# TiltyDuo.net
KiCad netlist of a schematic drawn in EAGLE
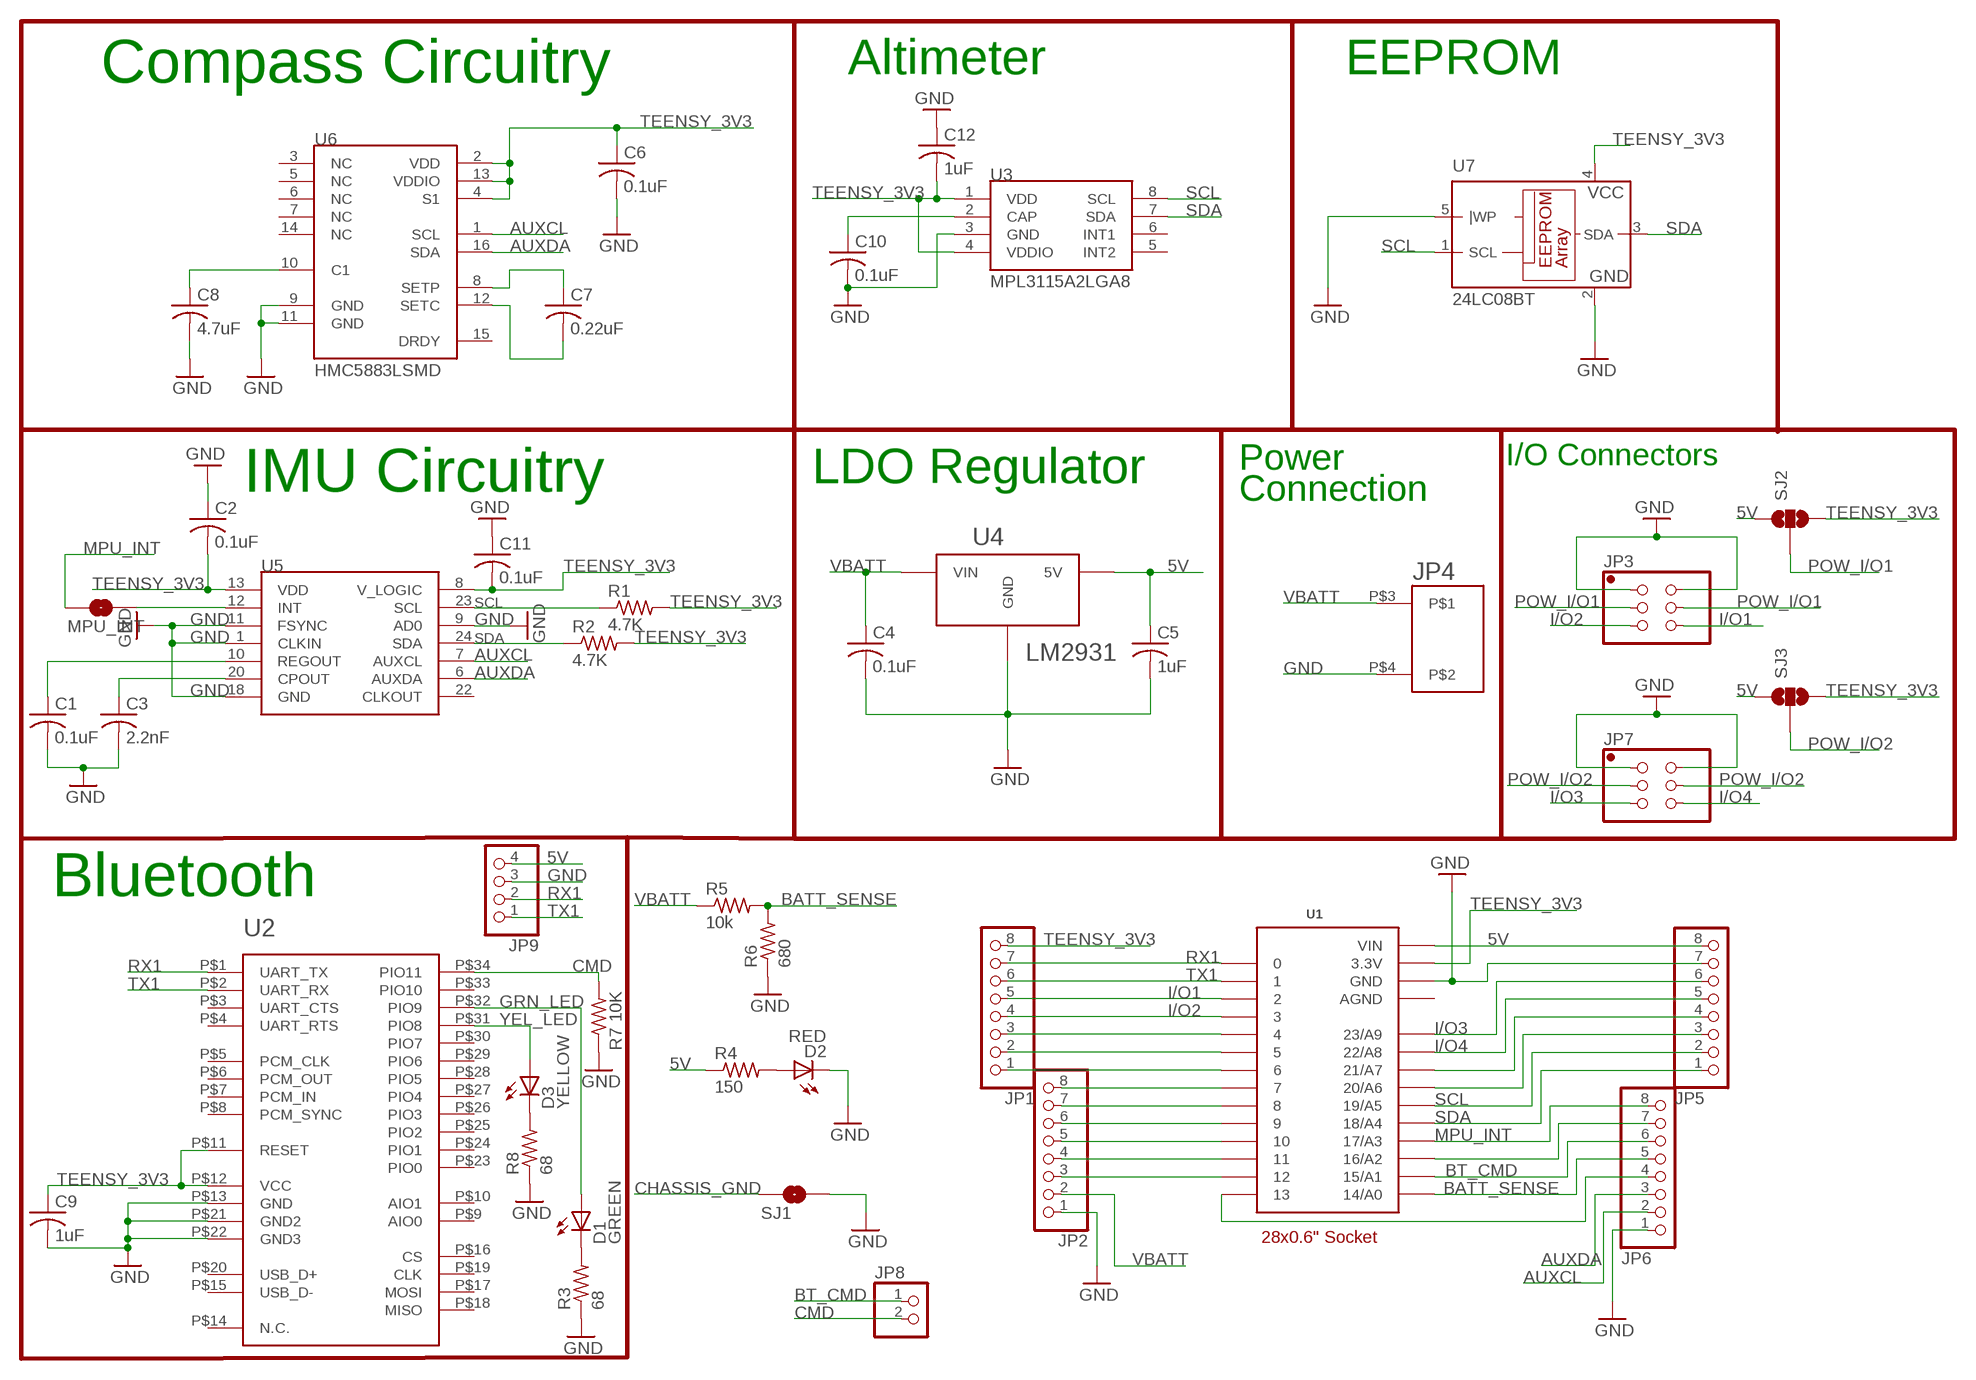
[diagram p0: schematic, sheet 1]

(export (version "E")
  (design (tool "Eeschema 10.0.6"))
  (components
    (comp (ref "C1")
      (value "0.1uF")
      (footprint "eagle-import:C0603")
      (libsource (lib "eagle-import") (part "C-USC0603"))
    )
    (comp (ref "C2")
      (value "0.1uF")
      (footprint "eagle-import:C0603")
      (libsource (lib "eagle-import") (part "C-USC0603"))
    )
    (comp (ref "C3")
      (value "2.2nF")
      (footprint "eagle-import:C0603")
      (libsource (lib "eagle-import") (part "C-USC0603"))
    )
    (comp (ref "C4")
      (value "0.1uF")
      (footprint "eagle-import:C0603")
      (libsource (lib "eagle-import") (part "C-USC0603"))
    )
    (comp (ref "C5")
      (value "1uF")
      (footprint "eagle-import:C0603")
      (libsource (lib "eagle-import") (part "C-USC0603"))
    )
    (comp (ref "C6")
      (value "0.1uF")
      (footprint "eagle-import:C0603")
      (libsource (lib "eagle-import") (part "C-USC0603"))
    )
    (comp (ref "C7")
      (value "0.22uF")
      (footprint "eagle-import:C0603")
      (libsource (lib "eagle-import") (part "C-USC0603"))
    )
    (comp (ref "C8")
      (value "4.7uF")
      (footprint "eagle-import:C0603")
      (libsource (lib "eagle-import") (part "C-USC0603"))
    )
    (comp (ref "C9")
      (value "1uF")
      (footprint "eagle-import:C0603")
      (libsource (lib "eagle-import") (part "C-USC0603"))
    )
    (comp (ref "C10")
      (value "0.1uF")
      (footprint "eagle-import:C0603")
      (libsource (lib "eagle-import") (part "C-USC0603"))
    )
    (comp (ref "C11")
      (value "0.1uF")
      (footprint "eagle-import:C0603")
      (libsource (lib "eagle-import") (part "C-USC0603"))
    )
    (comp (ref "C12")
      (value "1uF")
      (footprint "eagle-import:C0603")
      (libsource (lib "eagle-import") (part "C-USC0603"))
    )
    (comp (ref "D1")
      (value "GREEN")
      (footprint "eagle-import:LED-0805")
      (libsource (lib "eagle-import") (part "LED-GREENLED-0805_NO_SILK"))
    )
    (comp (ref "D2")
      (value "RED")
      (footprint "eagle-import:LED-0805")
      (libsource (lib "eagle-import") (part "LED-GREENLED-0805_NO_SILK"))
    )
    (comp (ref "D3")
      (value "YELLOW")
      (footprint "eagle-import:LED-0805")
      (libsource (lib "eagle-import") (part "LED-GREENLED-0805_NO_SILK"))
    )
    (comp (ref "JP1")
      (value "PINHD-1X81X08_NO_SILK")
      (footprint "eagle-import:1X08_NO_SS")
      (libsource (lib "eagle-import") (part "PINHD-1X81X08_NO_SILK"))
    )
    (comp (ref "JP2")
      (value "PINHD-1X81X08_NO_SILK")
      (footprint "eagle-import:1X08_NO_SS")
      (libsource (lib "eagle-import") (part "PINHD-1X81X08_NO_SILK"))
    )
    (comp (ref "JP3")
      (value "PINHD-2X32X03_NO_SILK")
      (footprint "eagle-import:2X03_NO_SS")
      (libsource (lib "eagle-import") (part "PINHD-2X32X03_NO_SILK"))
    )
    (comp (ref "JP4")
      (value "2-POS_SMD_TERM_BLOCK")
      (footprint "eagle-import:2-POS_SMD_TERMINAL_BLOCK")
      (libsource (lib "eagle-import") (part "2-POS_SMD_TERM_BLOCK"))
    )
    (comp (ref "JP5")
      (value "PINHD-1X81X08_NO_SILK")
      (footprint "eagle-import:1X08_NO_SS")
      (libsource (lib "eagle-import") (part "PINHD-1X81X08_NO_SILK"))
    )
    (comp (ref "JP6")
      (value "PINHD-1X81X08_NO_SILK")
      (footprint "eagle-import:1X08_NO_SS")
      (libsource (lib "eagle-import") (part "PINHD-1X81X08_NO_SILK"))
    )
    (comp (ref "JP7")
      (value "PINHD-2X32X03_NO_SILK")
      (footprint "eagle-import:2X03_NO_SS")
      (libsource (lib "eagle-import") (part "PINHD-2X32X03_NO_SILK"))
    )
    (comp (ref "JP8")
      (value "PINHD-1X21X02_NO_SILK")
      (footprint "eagle-import:1X02_NO_SS")
      (libsource (lib "eagle-import") (part "PINHD-1X21X02_NO_SILK"))
    )
    (comp (ref "JP9")
      (value "PINHD-1X4")
      (footprint "eagle-import:1X04")
      (libsource (lib "eagle-import") (part "PINHD-1X4"))
    )
    (comp (ref "MPU_INT")
      (value "SOLDERJUMPERNO")
      (footprint "eagle-import:SJ_2S-NO")
      (libsource (lib "eagle-import") (part "SOLDERJUMPERNO"))
    )
    (comp (ref "R1")
      (value "4.7K")
      (footprint "eagle-import:R0402")
      (libsource (lib "eagle-import") (part "R-US_R0402"))
    )
    (comp (ref "R2")
      (value "4.7K")
      (footprint "eagle-import:R0402")
      (libsource (lib "eagle-import") (part "R-US_R0402"))
    )
    (comp (ref "R3")
      (value "68")
      (footprint "eagle-import:R0603")
      (libsource (lib "eagle-import") (part "R-US_R0603"))
    )
    (comp (ref "R4")
      (value "150")
      (footprint "eagle-import:R0603")
      (libsource (lib "eagle-import") (part "R-US_R0603"))
    )
    (comp (ref "R5")
      (value "10k")
      (footprint "eagle-import:R0603")
      (libsource (lib "eagle-import") (part "R-US_R0603"))
    )
    (comp (ref "R6")
      (value "680")
      (footprint "eagle-import:R0603")
      (libsource (lib "eagle-import") (part "R-US_R0603"))
    )
    (comp (ref "R7")
      (value "10K")
      (footprint "eagle-import:R0603")
      (libsource (lib "eagle-import") (part "R-US_R0603"))
    )
    (comp (ref "R8")
      (value "68")
      (footprint "eagle-import:R0603")
      (libsource (lib "eagle-import") (part "R-US_R0603"))
    )
    (comp (ref "SJ1")
      (value "SOLDERJUMPERNO")
      (footprint "eagle-import:SJ_2S-NO")
      (libsource (lib "eagle-import") (part "SOLDERJUMPERNO"))
    )
    (comp (ref "SJ2")
      (value "SOLDERJUMPER_2WAYS")
      (footprint "eagle-import:SJ_3")
      (libsource (lib "eagle-import") (part "SOLDERJUMPER_2WAYS"))
    )
    (comp (ref "SJ3")
      (value "SOLDERJUMPER_2WAYS")
      (footprint "eagle-import:SJ_3")
      (libsource (lib "eagle-import") (part "SOLDERJUMPER_2WAYS"))
    )
    (comp (ref "U1")
      (value "TEENSY_3.0_OUTER-PINS28-DIP_SOCKET")
      (footprint "eagle-import:28-DIP")
      (libsource (lib "eagle-import") (part "TEENSY_3.0_OUTER-PINS28-DIP_SOCKET"))
    )
    (comp (ref "U2")
      (value "HC-09_BREAKOUT")
      (footprint "eagle-import:HC-09_BREAKOUT")
      (libsource (lib "eagle-import") (part "HC-09_BREAKOUT"))
    )
    (comp (ref "U3")
      (value "MPL3115A2LGA8")
      (footprint "eagle-import:LGA8")
      (libsource (lib "eagle-import") (part "MPL3115A2LGA8"))
    )
    (comp (ref "U4")
      (value "LM2931")
      (footprint "eagle-import:TO263")
      (libsource (lib "eagle-import") (part "LM2931"))
    )
    (comp (ref "U5")
      (value "MPU-6050")
      (footprint "eagle-import:QFN-24")
      (libsource (lib "eagle-import") (part "MPU-6050"))
    )
    (comp (ref "U6")
      (value "HMC5883LSMD")
      (footprint "eagle-import:16LPCC")
      (libsource (lib "eagle-import") (part "HMC5883LSMD"))
    )
    (comp (ref "U7")
      (value "24LC08BT")
      (footprint "eagle-import:SOT23-5L")
      (libsource (lib "eagle-import") (part "24LC08BT"))
    )
  )
  (nets
    (net (code "1") (name "/5V") (class "Default")
      (node (ref "C5") (pin "1") (pinfunction "1_1") (pintype "passive"))
      (node (ref "JP5") (pin "8") (pinfunction "8_8") (pintype "passive"))
      (node (ref "JP9") (pin "4") (pinfunction "4_4") (pintype "passive"))
      (node (ref "R4") (pin "1") (pinfunction "1_1") (pintype "passive"))
      (node (ref "SJ2") (pin "1") (pinfunction "1_1") (pintype "passive"))
      (node (ref "SJ3") (pin "1") (pinfunction "1_1") (pintype "passive"))
      (node (ref "U1") (pin "P$15") (pinfunction "VIN_P$15") (pintype "power_in"))
      (node (ref "U4") (pin "P$3") (pinfunction "5V_P$3") (pintype "bidirectional"))
    )
    (net (code "2") (name "/AGND") (class "Default")
      (node (ref "U1") (pin "P$16") (pinfunction "AGND_P$16") (pintype "power_in"))
    )
    (net (code "3") (name "/AUXCL") (class "Default")
      (node (ref "JP6") (pin "2") (pinfunction "2_2") (pintype "passive"))
      (node (ref "U5") (pin "7") (pinfunction "AUXCL_7") (pintype "bidirectional"))
      (node (ref "U6") (pin "1") (pinfunction "SCL_1") (pintype "bidirectional"))
    )
    (net (code "4") (name "/AUXDA") (class "Default")
      (node (ref "JP6") (pin "3") (pinfunction "3_3") (pintype "passive"))
      (node (ref "U5") (pin "6") (pinfunction "AUXDA_6") (pintype "bidirectional"))
      (node (ref "U6") (pin "16") (pinfunction "SDA_16") (pintype "bidirectional"))
    )
    (net (code "5") (name "/BATT_SENSE") (class "Default")
      (node (ref "JP6") (pin "5") (pinfunction "5_5") (pintype "passive"))
      (node (ref "R5") (pin "2") (pinfunction "2_2") (pintype "passive"))
      (node (ref "R6") (pin "2") (pinfunction "2_2") (pintype "passive"))
      (node (ref "U1") (pin "P$27") (pinfunction "14/A0_P$27") (pintype "bidirectional"))
    )
    (net (code "6") (name "/BT_CMD") (class "Default")
      (node (ref "JP6") (pin "6") (pinfunction "6_6") (pintype "passive"))
      (node (ref "JP8") (pin "1") (pinfunction "1_1") (pintype "passive"))
      (node (ref "U1") (pin "P$26") (pinfunction "15/A1_P$26") (pintype "bidirectional"))
    )
    (net (code "7") (name "/CHASSIS_GND") (class "Default")
      (node (ref "SJ1") (pin "1") (pinfunction "1_1") (pintype "passive"))
    )
    (net (code "8") (name "/CMD") (class "Default")
      (node (ref "JP8") (pin "2") (pinfunction "2_2") (pintype "passive"))
      (node (ref "R7") (pin "2") (pinfunction "2_2") (pintype "passive"))
      (node (ref "U2") (pin "P$34") (pinfunction "PIO11_P$34") (pintype "bidirectional"))
    )
    (net (code "9") (name "/GRN_LED") (class "Default")
      (node (ref "D1") (pin "1") (pinfunction "A_1") (pintype "passive"))
      (node (ref "U2") (pin "P$32") (pinfunction "PIO9_P$32") (pintype "bidirectional"))
    )
    (net (code "10") (name "/I{slash}O1") (class "Default")
      (node (ref "JP1") (pin "5") (pinfunction "5_5") (pintype "passive"))
      (node (ref "JP3") (pin "6") (pinfunction "6_6") (pintype "passive"))
      (node (ref "U1") (pin "P$4") (pinfunction "2_P$4") (pintype "bidirectional"))
    )
    (net (code "11") (name "/I{slash}O2") (class "Default")
      (node (ref "JP1") (pin "4") (pinfunction "4_4") (pintype "passive"))
      (node (ref "JP3") (pin "5") (pinfunction "5_5") (pintype "passive"))
      (node (ref "U1") (pin "P$5") (pinfunction "3_P$5") (pintype "bidirectional"))
    )
    (net (code "12") (name "/I{slash}O3") (class "Default")
      (node (ref "JP5") (pin "6") (pinfunction "6_6") (pintype "passive"))
      (node (ref "JP7") (pin "5") (pinfunction "5_5") (pintype "passive"))
      (node (ref "U1") (pin "P$18") (pinfunction "23/A9_P$18") (pintype "bidirectional"))
    )
    (net (code "13") (name "/I{slash}O4") (class "Default")
      (node (ref "JP5") (pin "5") (pinfunction "5_5") (pintype "passive"))
      (node (ref "JP7") (pin "6") (pinfunction "6_6") (pintype "passive"))
      (node (ref "U1") (pin "P$19") (pinfunction "22/A8_P$19") (pintype "bidirectional"))
    )
    (net (code "14") (name "/MPU_INT") (class "Default")
      (node (ref "JP6") (pin "8") (pinfunction "8_8") (pintype "passive"))
      (node (ref "MPU_INT") (pin "1") (pinfunction "1_1") (pintype "passive"))
      (node (ref "U1") (pin "P$24") (pinfunction "17/A3_P$24") (pintype "bidirectional"))
    )
    (net (code "15") (name "/POW_I{slash}O1") (class "Default")
      (node (ref "JP3") (pin "3") (pinfunction "3_3") (pintype "passive"))
      (node (ref "JP3") (pin "4") (pinfunction "4_4") (pintype "passive"))
      (node (ref "SJ2") (pin "2") (pinfunction "2_2") (pintype "passive"))
    )
    (net (code "16") (name "/POW_I{slash}O2") (class "Default")
      (node (ref "JP7") (pin "3") (pinfunction "3_3") (pintype "passive"))
      (node (ref "JP7") (pin "4") (pinfunction "4_4") (pintype "passive"))
      (node (ref "SJ3") (pin "2") (pinfunction "2_2") (pintype "passive"))
    )
    (net (code "17") (name "/RX1") (class "Default")
      (node (ref "JP1") (pin "7") (pinfunction "7_7") (pintype "passive"))
      (node (ref "JP9") (pin "2") (pinfunction "2_2") (pintype "passive"))
      (node (ref "U1") (pin "P$2") (pinfunction "0_P$2") (pintype "bidirectional"))
      (node (ref "U2") (pin "P$1") (pinfunction "UART_TX_P$1") (pintype "bidirectional"))
    )
    (net (code "18") (name "/SCL") (class "Default")
      (node (ref "JP5") (pin "2") (pinfunction "2_2") (pintype "passive"))
      (node (ref "R1") (pin "1") (pinfunction "1_1") (pintype "passive"))
      (node (ref "U1") (pin "P$22") (pinfunction "19/A5_P$22") (pintype "bidirectional"))
      (node (ref "U3") (pin "8") (pinfunction "SCL_8") (pintype "bidirectional"))
      (node (ref "U5") (pin "23") (pinfunction "SCL_23") (pintype "bidirectional"))
      (node (ref "U7") (pin "1") (pinfunction "SCL_1") (pintype "input"))
    )
    (net (code "19") (name "/SDA") (class "Default")
      (node (ref "JP5") (pin "1") (pinfunction "1_1") (pintype "passive"))
      (node (ref "R2") (pin "1") (pinfunction "1_1") (pintype "passive"))
      (node (ref "U1") (pin "P$23") (pinfunction "18/A4_P$23") (pintype "bidirectional"))
      (node (ref "U3") (pin "7") (pinfunction "SDA_7") (pintype "bidirectional"))
      (node (ref "U5") (pin "24") (pinfunction "SDA_24") (pintype "bidirectional"))
      (node (ref "U7") (pin "3") (pinfunction "SDA_3") (pintype "bidirectional"))
    )
    (net (code "20") (name "/TEENSY_3V3") (class "Default")
      (node (ref "C11") (pin "2") (pinfunction "2_2") (pintype "passive"))
      (node (ref "C12") (pin "2") (pinfunction "2_2") (pintype "passive"))
      (node (ref "C2") (pin "2") (pinfunction "2_2") (pintype "passive"))
      (node (ref "C6") (pin "1") (pinfunction "1_1") (pintype "passive"))
      (node (ref "C9") (pin "1") (pinfunction "1_1") (pintype "passive"))
      (node (ref "JP1") (pin "8") (pinfunction "8_8") (pintype "passive"))
      (node (ref "R1") (pin "2") (pinfunction "2_2") (pintype "passive"))
      (node (ref "R2") (pin "2") (pinfunction "2_2") (pintype "passive"))
      (node (ref "SJ2") (pin "3") (pinfunction "3_3") (pintype "passive"))
      (node (ref "SJ3") (pin "3") (pinfunction "3_3") (pintype "passive"))
      (node (ref "U1") (pin "P$17") (pinfunction "3.3V_P$17") (pintype "power_in"))
      (node (ref "U2") (pin "P$11") (pinfunction "RESET_P$11") (pintype "bidirectional"))
      (node (ref "U2") (pin "P$12") (pinfunction "VCC_P$12") (pintype "bidirectional"))
      (node (ref "U3") (pin "1") (pinfunction "VDD_1") (pintype "bidirectional"))
      (node (ref "U3") (pin "4") (pinfunction "VDDIO_4") (pintype "bidirectional"))
      (node (ref "U5") (pin "13") (pinfunction "VDD_13") (pintype "bidirectional"))
      (node (ref "U5") (pin "8") (pinfunction "V_LOGIC_8") (pintype "bidirectional"))
      (node (ref "U6") (pin "13") (pinfunction "VDDIO_13") (pintype "bidirectional"))
      (node (ref "U6") (pin "2") (pinfunction "VDD_2") (pintype "bidirectional"))
      (node (ref "U6") (pin "4") (pinfunction "S1_4") (pintype "bidirectional"))
      (node (ref "U7") (pin "4") (pinfunction "VCC_4") (pintype "power_in"))
    )
    (net (code "21") (name "/TX1") (class "Default")
      (node (ref "JP1") (pin "6") (pinfunction "6_6") (pintype "passive"))
      (node (ref "JP9") (pin "1") (pinfunction "1_1") (pintype "passive"))
      (node (ref "U1") (pin "P$3") (pinfunction "1_P$3") (pintype "bidirectional"))
      (node (ref "U2") (pin "P$2") (pinfunction "UART_RX_P$2") (pintype "bidirectional"))
    )
    (net (code "22") (name "/VBATT") (class "Default")
      (node (ref "C4") (pin "1") (pinfunction "1_1") (pintype "passive"))
      (node (ref "JP2") (pin "2") (pinfunction "2_2") (pintype "passive"))
      (node (ref "JP4") (pin "P$3") (pinfunction "P$1_P$3") (pintype "bidirectional"))
      (node (ref "R5") (pin "1") (pinfunction "1_1") (pintype "passive"))
      (node (ref "U4") (pin "P$2") (pinfunction "VIN_P$2") (pintype "bidirectional"))
    )
    (net (code "23") (name "/YEL_LED") (class "Default")
      (node (ref "D3") (pin "1") (pinfunction "A_1") (pintype "passive"))
      (node (ref "U2") (pin "P$31") (pinfunction "PIO8_P$31") (pintype "bidirectional"))
    )
    (net (code "24") (name "GND") (class "Default")
      (node (ref "C1") (pin "2") (pinfunction "2_2") (pintype "passive"))
      (node (ref "C10") (pin "2") (pinfunction "2_2") (pintype "passive"))
      (node (ref "C11") (pin "1") (pinfunction "1_1") (pintype "passive"))
      (node (ref "C12") (pin "1") (pinfunction "1_1") (pintype "passive"))
      (node (ref "C2") (pin "1") (pinfunction "1_1") (pintype "passive"))
      (node (ref "C3") (pin "2") (pinfunction "2_2") (pintype "passive"))
      (node (ref "C4") (pin "2") (pinfunction "2_2") (pintype "passive"))
      (node (ref "C5") (pin "2") (pinfunction "2_2") (pintype "passive"))
      (node (ref "C6") (pin "2") (pinfunction "2_2") (pintype "passive"))
      (node (ref "C8") (pin "2") (pinfunction "2_2") (pintype "passive"))
      (node (ref "C9") (pin "2") (pinfunction "2_2") (pintype "passive"))
      (node (ref "D2") (pin "2") (pinfunction "C_2") (pintype "passive"))
      (node (ref "JP2") (pin "1") (pinfunction "1_1") (pintype "passive"))
      (node (ref "JP3") (pin "1") (pinfunction "1_1") (pintype "passive"))
      (node (ref "JP3") (pin "2") (pinfunction "2_2") (pintype "passive"))
      (node (ref "JP4") (pin "P$4") (pinfunction "P$2_P$4") (pintype "bidirectional"))
      (node (ref "JP5") (pin "7") (pinfunction "7_7") (pintype "passive"))
      (node (ref "JP6") (pin "1") (pinfunction "1_1") (pintype "passive"))
      (node (ref "JP7") (pin "1") (pinfunction "1_1") (pintype "passive"))
      (node (ref "JP7") (pin "2") (pinfunction "2_2") (pintype "passive"))
      (node (ref "JP9") (pin "3") (pinfunction "3_3") (pintype "passive"))
      (node (ref "R3") (pin "1") (pinfunction "1_1") (pintype "passive"))
      (node (ref "R6") (pin "1") (pinfunction "1_1") (pintype "passive"))
      (node (ref "R7") (pin "1") (pinfunction "1_1") (pintype "passive"))
      (node (ref "R8") (pin "1") (pinfunction "1_1") (pintype "passive"))
      (node (ref "SJ1") (pin "2") (pinfunction "2_2") (pintype "passive"))
      (node (ref "U1") (pin "P$1") (pinfunction "GND_P$1") (pintype "power_in"))
      (node (ref "U2") (pin "P$13") (pinfunction "GND_P$13") (pintype "bidirectional"))
      (node (ref "U2") (pin "P$21") (pinfunction "GND2_P$21") (pintype "bidirectional"))
      (node (ref "U2") (pin "P$22") (pinfunction "GND3_P$22") (pintype "bidirectional"))
      (node (ref "U3") (pin "3") (pinfunction "GND_3") (pintype "bidirectional"))
      (node (ref "U4") (pin "P$1") (pinfunction "GND_P$1") (pintype "bidirectional"))
      (node (ref "U5") (pin "1") (pinfunction "CLKIN_1") (pintype "bidirectional"))
      (node (ref "U5") (pin "11") (pinfunction "FSYNC_11") (pintype "bidirectional"))
      (node (ref "U5") (pin "18") (pinfunction "GND_18") (pintype "bidirectional"))
      (node (ref "U5") (pin "9") (pinfunction "AD0_9") (pintype "bidirectional"))
      (node (ref "U6") (pin "11") (pinfunction "GND_11") (pintype "bidirectional"))
      (node (ref "U6") (pin "9") (pinfunction "GND_9") (pintype "bidirectional"))
      (node (ref "U7") (pin "2") (pinfunction "GND_2") (pintype "power_in"))
      (node (ref "U7") (pin "5") (pinfunction "|WP_5") (pintype "input"))
    )
    (net (code "25") (name "Net-(D1-C)") (class "Default")
      (node (ref "D1") (pin "2") (pinfunction "C_2") (pintype "passive"))
      (node (ref "R3") (pin "2") (pinfunction "2_2") (pintype "passive"))
    )
    (net (code "26") (name "Net-(D2-A)") (class "Default")
      (node (ref "D2") (pin "1") (pinfunction "A_1") (pintype "passive"))
      (node (ref "R4") (pin "2") (pinfunction "2_2") (pintype "passive"))
    )
    (net (code "27") (name "Net-(D3-C)") (class "Default")
      (node (ref "D3") (pin "2") (pinfunction "C_2") (pintype "passive"))
      (node (ref "R8") (pin "2") (pinfunction "2_2") (pintype "passive"))
    )
    (net (code "28") (name "Net-(U1-4)") (class "Default")
      (node (ref "JP1") (pin "3") (pinfunction "3_3") (pintype "passive"))
      (node (ref "U1") (pin "P$6") (pinfunction "4_P$6") (pintype "bidirectional"))
    )
    (net (code "29") (name "Net-(U1-5)") (class "Default")
      (node (ref "JP1") (pin "2") (pinfunction "2_2") (pintype "passive"))
      (node (ref "U1") (pin "P$7") (pinfunction "5_P$7") (pintype "bidirectional"))
    )
    (net (code "30") (name "Net-(U1-6)") (class "Default")
      (node (ref "JP1") (pin "1") (pinfunction "1_1") (pintype "passive"))
      (node (ref "U1") (pin "P$8") (pinfunction "6_P$8") (pintype "bidirectional"))
    )
    (net (code "31") (name "Net-(U1-7)") (class "Default")
      (node (ref "JP2") (pin "8") (pinfunction "8_8") (pintype "passive"))
      (node (ref "U1") (pin "P$9") (pinfunction "7_P$9") (pintype "bidirectional"))
    )
    (net (code "32") (name "Net-(U1-8)") (class "Default")
      (node (ref "JP2") (pin "7") (pinfunction "7_7") (pintype "passive"))
      (node (ref "U1") (pin "P$10") (pinfunction "8_P$10") (pintype "bidirectional"))
    )
    (net (code "33") (name "Net-(U1-9)") (class "Default")
      (node (ref "JP2") (pin "6") (pinfunction "6_6") (pintype "passive"))
      (node (ref "U1") (pin "P$11") (pinfunction "9_P$11") (pintype "bidirectional"))
    )
    (net (code "34") (name "Net-(U1-10)") (class "Default")
      (node (ref "JP2") (pin "5") (pinfunction "5_5") (pintype "passive"))
      (node (ref "U1") (pin "P$12") (pinfunction "10_P$12") (pintype "bidirectional"))
    )
    (net (code "35") (name "Net-(U1-11)") (class "Default")
      (node (ref "JP2") (pin "4") (pinfunction "4_4") (pintype "passive"))
      (node (ref "U1") (pin "P$13") (pinfunction "11_P$13") (pintype "bidirectional"))
    )
    (net (code "36") (name "Net-(U1-12)") (class "Default")
      (node (ref "JP2") (pin "3") (pinfunction "3_3") (pintype "passive"))
      (node (ref "U1") (pin "P$14") (pinfunction "12_P$14") (pintype "bidirectional"))
    )
    (net (code "37") (name "Net-(U1-13)") (class "Default")
      (node (ref "JP6") (pin "4") (pinfunction "4_4") (pintype "passive"))
      (node (ref "U1") (pin "P$28") (pinfunction "13_P$28") (pintype "bidirectional"))
    )
    (net (code "38") (name "Net-(U1-16{slash}A2)") (class "Default")
      (node (ref "JP6") (pin "7") (pinfunction "7_7") (pintype "passive"))
      (node (ref "U1") (pin "P$25") (pinfunction "16/A2_P$25") (pintype "bidirectional"))
    )
    (net (code "39") (name "Net-(U1-20{slash}A6)") (class "Default")
      (node (ref "JP5") (pin "3") (pinfunction "3_3") (pintype "passive"))
      (node (ref "U1") (pin "P$21") (pinfunction "20/A6_P$21") (pintype "bidirectional"))
    )
    (net (code "40") (name "Net-(U1-21{slash}A7)") (class "Default")
      (node (ref "JP5") (pin "4") (pinfunction "4_4") (pintype "passive"))
      (node (ref "U1") (pin "P$20") (pinfunction "21/A7_P$20") (pintype "bidirectional"))
    )
    (net (code "41") (name "Net-(U3-CAP)") (class "Default")
      (node (ref "C10") (pin "1") (pinfunction "1_1") (pintype "passive"))
      (node (ref "U3") (pin "2") (pinfunction "CAP_2") (pintype "bidirectional"))
    )
    (net (code "42") (name "Net-(U5-CPOUT)") (class "Default")
      (node (ref "C3") (pin "1") (pinfunction "1_1") (pintype "passive"))
      (node (ref "U5") (pin "20") (pinfunction "CPOUT_20") (pintype "bidirectional"))
    )
    (net (code "43") (name "Net-(U5-INT)") (class "Default")
      (node (ref "MPU_INT") (pin "2") (pinfunction "2_2") (pintype "passive"))
      (node (ref "U5") (pin "12") (pinfunction "INT_12") (pintype "bidirectional"))
    )
    (net (code "44") (name "Net-(U5-REGOUT)") (class "Default")
      (node (ref "C1") (pin "1") (pinfunction "1_1") (pintype "passive"))
      (node (ref "U5") (pin "10") (pinfunction "REGOUT_10") (pintype "bidirectional"))
    )
    (net (code "45") (name "Net-(U6-C1)") (class "Default")
      (node (ref "C8") (pin "1") (pinfunction "1_1") (pintype "passive"))
      (node (ref "U6") (pin "10") (pinfunction "C1_10") (pintype "bidirectional"))
    )
    (net (code "46") (name "Net-(U6-SETC)") (class "Default")
      (node (ref "C7") (pin "2") (pinfunction "2_2") (pintype "passive"))
      (node (ref "U6") (pin "12") (pinfunction "SETC_12") (pintype "bidirectional"))
    )
    (net (code "47") (name "Net-(U6-SETP)") (class "Default")
      (node (ref "C7") (pin "1") (pinfunction "1_1") (pintype "passive"))
      (node (ref "U6") (pin "8") (pinfunction "SETP_8") (pintype "bidirectional"))
    )
    (net (code "48") (name "unconnected-(U2-AIO0-PadP$9)") (class "Default")
      (node (ref "U2") (pin "P$9") (pinfunction "AIO0_P$9") (pintype "bidirectional"))
    )
    (net (code "49") (name "unconnected-(U2-AIO1-PadP$10)") (class "Default")
      (node (ref "U2") (pin "P$10") (pinfunction "AIO1_P$10") (pintype "bidirectional"))
    )
    (net (code "50") (name "unconnected-(U2-CLK-PadP$19)") (class "Default")
      (node (ref "U2") (pin "P$19") (pinfunction "CLK_P$19") (pintype "bidirectional"))
    )
    (net (code "51") (name "unconnected-(U2-CS-PadP$16)") (class "Default")
      (node (ref "U2") (pin "P$16") (pinfunction "CS_P$16") (pintype "bidirectional"))
    )
    (net (code "52") (name "unconnected-(U2-MISO-PadP$18)") (class "Default")
      (node (ref "U2") (pin "P$18") (pinfunction "MISO_P$18") (pintype "bidirectional"))
    )
    (net (code "53") (name "unconnected-(U2-MOSI-PadP$17)") (class "Default")
      (node (ref "U2") (pin "P$17") (pinfunction "MOSI_P$17") (pintype "bidirectional"))
    )
    (net (code "54") (name "unconnected-(U2-N.C.-PadP$14)") (class "Default")
      (node (ref "U2") (pin "P$14") (pinfunction "N.C._P$14") (pintype "bidirectional"))
    )
    (net (code "55") (name "unconnected-(U2-PCM_CLK-PadP$5)") (class "Default")
      (node (ref "U2") (pin "P$5") (pinfunction "PCM_CLK_P$5") (pintype "bidirectional"))
    )
    (net (code "56") (name "unconnected-(U2-PCM_IN-PadP$7)") (class "Default")
      (node (ref "U2") (pin "P$7") (pinfunction "PCM_IN_P$7") (pintype "bidirectional"))
    )
    (net (code "57") (name "unconnected-(U2-PCM_OUT-PadP$6)") (class "Default")
      (node (ref "U2") (pin "P$6") (pinfunction "PCM_OUT_P$6") (pintype "bidirectional"))
    )
    (net (code "58") (name "unconnected-(U2-PCM_SYNC-PadP$8)") (class "Default")
      (node (ref "U2") (pin "P$8") (pinfunction "PCM_SYNC_P$8") (pintype "bidirectional"))
    )
    (net (code "59") (name "unconnected-(U2-PIO0-PadP$23)") (class "Default")
      (node (ref "U2") (pin "P$23") (pinfunction "PIO0_P$23") (pintype "bidirectional"))
    )
    (net (code "60") (name "unconnected-(U2-PIO1-PadP$24)") (class "Default")
      (node (ref "U2") (pin "P$24") (pinfunction "PIO1_P$24") (pintype "bidirectional"))
    )
    (net (code "61") (name "unconnected-(U2-PIO2-PadP$25)") (class "Default")
      (node (ref "U2") (pin "P$25") (pinfunction "PIO2_P$25") (pintype "bidirectional"))
    )
    (net (code "62") (name "unconnected-(U2-PIO3-PadP$26)") (class "Default")
      (node (ref "U2") (pin "P$26") (pinfunction "PIO3_P$26") (pintype "bidirectional"))
    )
    (net (code "63") (name "unconnected-(U2-PIO4-PadP$27)") (class "Default")
      (node (ref "U2") (pin "P$27") (pinfunction "PIO4_P$27") (pintype "bidirectional"))
    )
    (net (code "64") (name "unconnected-(U2-PIO5-PadP$28)") (class "Default")
      (node (ref "U2") (pin "P$28") (pinfunction "PIO5_P$28") (pintype "bidirectional"))
    )
    (net (code "65") (name "unconnected-(U2-PIO6-PadP$29)") (class "Default")
      (node (ref "U2") (pin "P$29") (pinfunction "PIO6_P$29") (pintype "bidirectional"))
    )
    (net (code "66") (name "unconnected-(U2-PIO7-PadP$30)") (class "Default")
      (node (ref "U2") (pin "P$30") (pinfunction "PIO7_P$30") (pintype "bidirectional"))
    )
    (net (code "67") (name "unconnected-(U2-PIO10-PadP$33)") (class "Default")
      (node (ref "U2") (pin "P$33") (pinfunction "PIO10_P$33") (pintype "bidirectional"))
    )
    (net (code "68") (name "unconnected-(U2-UART_CTS-PadP$3)") (class "Default")
      (node (ref "U2") (pin "P$3") (pinfunction "UART_CTS_P$3") (pintype "bidirectional"))
    )
    (net (code "69") (name "unconnected-(U2-UART_RTS-PadP$4)") (class "Default")
      (node (ref "U2") (pin "P$4") (pinfunction "UART_RTS_P$4") (pintype "bidirectional"))
    )
    (net (code "70") (name "unconnected-(U2-USB_D+-PadP$20)") (class "Default")
      (node (ref "U2") (pin "P$20") (pinfunction "USB_D+_P$20") (pintype "bidirectional"))
    )
    (net (code "71") (name "unconnected-(U2-USB_D--PadP$15)") (class "Default")
      (node (ref "U2") (pin "P$15") (pinfunction "USB_D-_P$15") (pintype "bidirectional"))
    )
    (net (code "72") (name "unconnected-(U3-INT1-Pad6)") (class "Default")
      (node (ref "U3") (pin "6") (pinfunction "INT1_6") (pintype "bidirectional"))
    )
    (net (code "73") (name "unconnected-(U3-INT2-Pad5)") (class "Default")
      (node (ref "U3") (pin "5") (pinfunction "INT2_5") (pintype "bidirectional"))
    )
    (net (code "74") (name "unconnected-(U5-CLKOUT-Pad22)") (class "Default")
      (node (ref "U5") (pin "22") (pinfunction "CLKOUT_22") (pintype "bidirectional"))
    )
    (net (code "75") (name "unconnected-(U6-DRDY-Pad15)") (class "Default")
      (node (ref "U6") (pin "15") (pinfunction "DRDY_15") (pintype "bidirectional"))
    )
    (net (code "76") (name "unconnected-(U6-NC-Pad3)") (class "Default")
      (node (ref "U6") (pin "3") (pinfunction "NC_3") (pintype "bidirectional"))
    )
    (net (code "77") (name "unconnected-(U6-NC-Pad5)") (class "Default")
      (node (ref "U6") (pin "5") (pinfunction "NC_5") (pintype "bidirectional"))
    )
    (net (code "78") (name "unconnected-(U6-NC-Pad6)") (class "Default")
      (node (ref "U6") (pin "6") (pinfunction "NC_6") (pintype "bidirectional"))
    )
    (net (code "79") (name "unconnected-(U6-NC-Pad7)") (class "Default")
      (node (ref "U6") (pin "7") (pinfunction "NC_7") (pintype "bidirectional"))
    )
    (net (code "80") (name "unconnected-(U6-NC-Pad14)") (class "Default")
      (node (ref "U6") (pin "14") (pinfunction "NC_14") (pintype "bidirectional"))
    )
  )
)
